# MCH_FPGA_Decoupling.net
KiCad netlist of a schematic drawn in Altium Designer
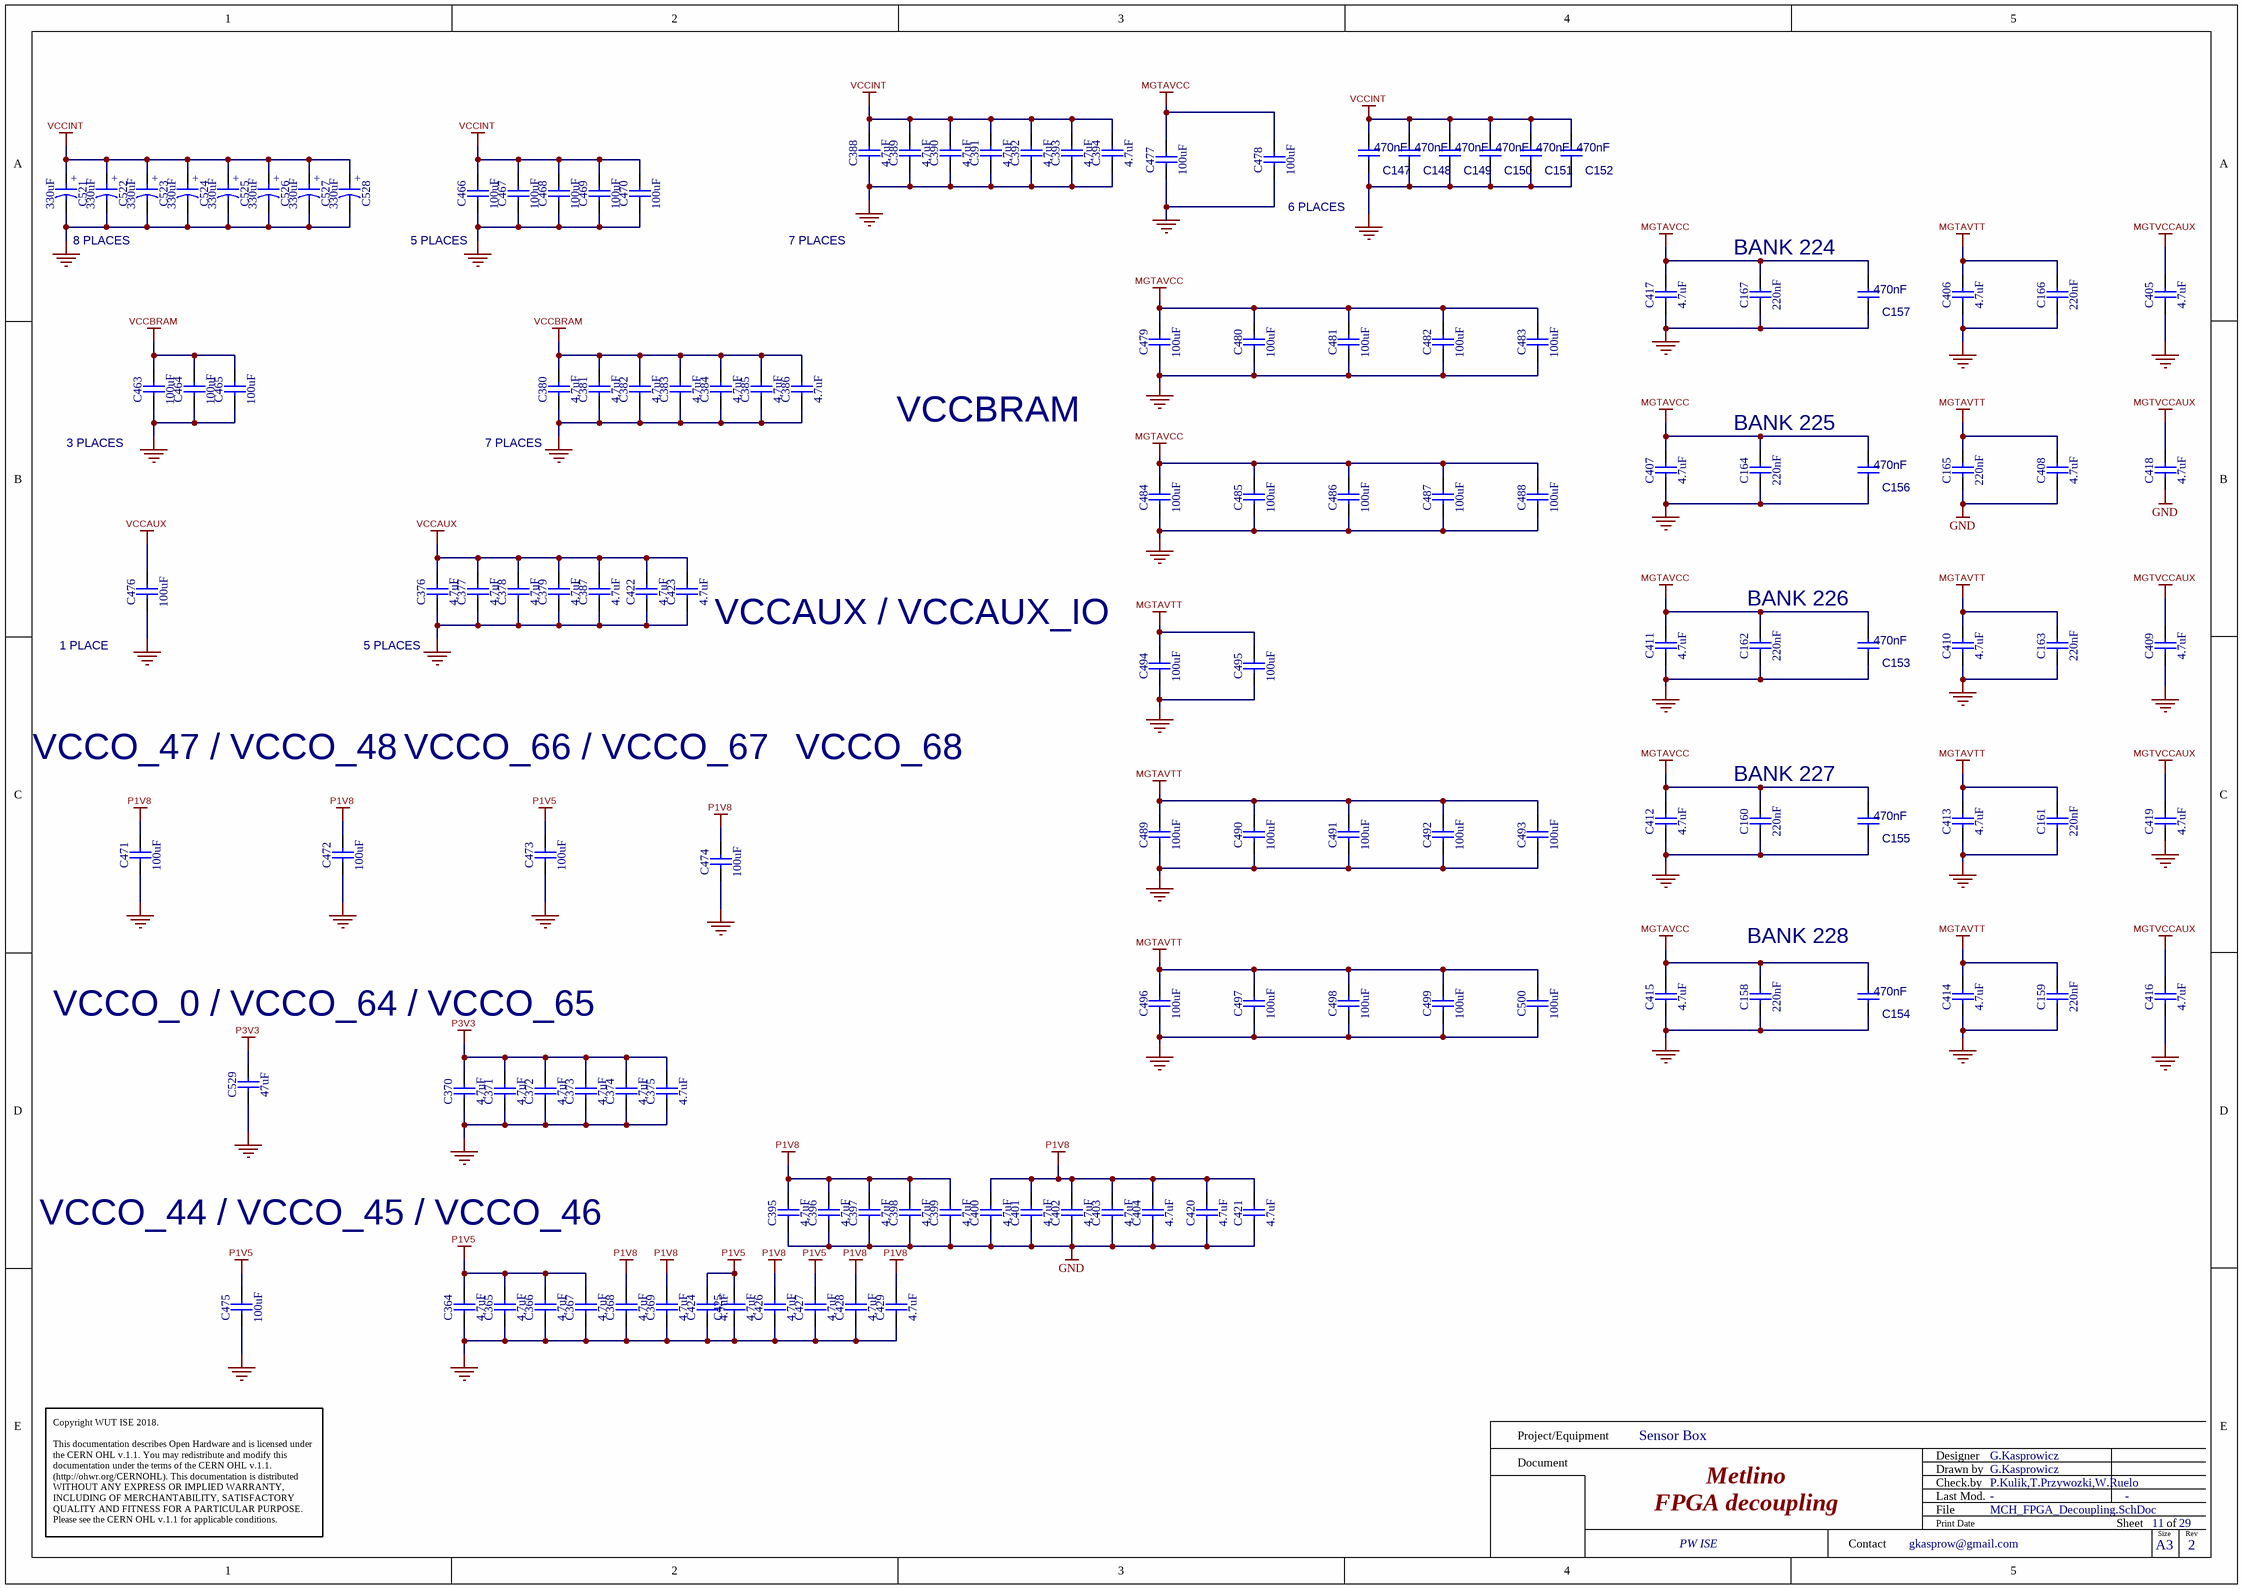
[diagram p0: MCH_FPGA_Decoupling.SchDoc]

(export (version "E")
  (design (tool "Eeschema 10.0.6"))
  (components
    (comp (ref "C147")
      (value "470nF")
      (footprint "CAPC0603X33N")
      (fields
        (field (name "$$NOTCOMMONPROPERTY_GENERAL PART NUMBER") "CC0201_470NF_4V_20%_X5R")
        (field (name "$$NOTCOMMONPROPERTY_MANUFACTURER1 PART NUMBER") "AMK063BJ474MP-F")
        (field (name "MANUFACTURER") "GENERIC")
      )
      (libsource (lib "altium-import") (part "root_1__*"))
    )
    (comp (ref "C148")
      (value "470nF")
      (footprint "CAPC0603X33N")
      (fields
        (field (name "$$NOTCOMMONPROPERTY_GENERAL PART NUMBER") "CC0201_470NF_4V_20%_X5R")
        (field (name "$$NOTCOMMONPROPERTY_MANUFACTURER1 PART NUMBER") "AMK063BJ474MP-F")
        (field (name "MANUFACTURER") "GENERIC")
      )
      (libsource (lib "altium-import") (part "root_1__*"))
    )
    (comp (ref "C149")
      (value "470nF")
      (footprint "CAPC0603X33N")
      (fields
        (field (name "$$NOTCOMMONPROPERTY_GENERAL PART NUMBER") "CC0201_470NF_4V_20%_X5R")
        (field (name "$$NOTCOMMONPROPERTY_MANUFACTURER1 PART NUMBER") "AMK063BJ474MP-F")
        (field (name "MANUFACTURER") "GENERIC")
      )
      (libsource (lib "altium-import") (part "root_1__*"))
    )
    (comp (ref "C150")
      (value "470nF")
      (footprint "CAPC0603X33N")
      (fields
        (field (name "$$NOTCOMMONPROPERTY_GENERAL PART NUMBER") "CC0201_470NF_4V_20%_X5R")
        (field (name "$$NOTCOMMONPROPERTY_MANUFACTURER1 PART NUMBER") "AMK063BJ474MP-F")
        (field (name "MANUFACTURER") "GENERIC")
      )
      (libsource (lib "altium-import") (part "root_1__*"))
    )
    (comp (ref "C151")
      (value "470nF")
      (footprint "CAPC0603X33N")
      (fields
        (field (name "$$NOTCOMMONPROPERTY_GENERAL PART NUMBER") "CC0201_470NF_4V_20%_X5R")
        (field (name "$$NOTCOMMONPROPERTY_MANUFACTURER1 PART NUMBER") "AMK063BJ474MP-F")
        (field (name "MANUFACTURER") "GENERIC")
      )
      (libsource (lib "altium-import") (part "root_1__*"))
    )
    (comp (ref "C152")
      (value "470nF")
      (footprint "CAPC0603X33N")
      (fields
        (field (name "$$NOTCOMMONPROPERTY_GENERAL PART NUMBER") "CC0201_470NF_4V_20%_X5R")
        (field (name "$$NOTCOMMONPROPERTY_MANUFACTURER1 PART NUMBER") "AMK063BJ474MP-F")
        (field (name "MANUFACTURER") "GENERIC")
      )
      (libsource (lib "altium-import") (part "root_1__*"))
    )
    (comp (ref "C153")
      (value "470nF")
      (footprint "CAPC0603X33N")
      (fields
        (field (name "$$NOTCOMMONPROPERTY_GENERAL PART NUMBER") "CC0201_470NF_4V_20%_X5R")
        (field (name "$$NOTCOMMONPROPERTY_MANUFACTURER1 PART NUMBER") "AMK063BJ474MP-F")
        (field (name "MANUFACTURER") "GENERIC")
      )
      (libsource (lib "altium-import") (part "root_1__*"))
    )
    (comp (ref "C154")
      (value "470nF")
      (footprint "CAPC0603X33N")
      (fields
        (field (name "$$NOTCOMMONPROPERTY_GENERAL PART NUMBER") "CC0201_470NF_4V_20%_X5R")
        (field (name "$$NOTCOMMONPROPERTY_MANUFACTURER1 PART NUMBER") "AMK063BJ474MP-F")
        (field (name "MANUFACTURER") "GENERIC")
      )
      (libsource (lib "altium-import") (part "root_1__*"))
    )
    (comp (ref "C155")
      (value "470nF")
      (footprint "CAPC0603X33N")
      (fields
        (field (name "$$NOTCOMMONPROPERTY_GENERAL PART NUMBER") "CC0201_470NF_4V_20%_X5R")
        (field (name "$$NOTCOMMONPROPERTY_MANUFACTURER1 PART NUMBER") "AMK063BJ474MP-F")
        (field (name "MANUFACTURER") "GENERIC")
      )
      (libsource (lib "altium-import") (part "root_1__*"))
    )
    (comp (ref "C156")
      (value "470nF")
      (footprint "CAPC0603X33N")
      (fields
        (field (name "$$NOTCOMMONPROPERTY_GENERAL PART NUMBER") "CC0201_470NF_4V_20%_X5R")
        (field (name "$$NOTCOMMONPROPERTY_MANUFACTURER1 PART NUMBER") "AMK063BJ474MP-F")
        (field (name "MANUFACTURER") "GENERIC")
      )
      (libsource (lib "altium-import") (part "root_1__*"))
    )
    (comp (ref "C157")
      (value "470nF")
      (footprint "CAPC0603X33N")
      (fields
        (field (name "$$NOTCOMMONPROPERTY_GENERAL PART NUMBER") "CC0201_470NF_4V_20%_X5R")
        (field (name "$$NOTCOMMONPROPERTY_MANUFACTURER1 PART NUMBER") "AMK063BJ474MP-F")
        (field (name "MANUFACTURER") "GENERIC")
      )
      (libsource (lib "altium-import") (part "root_1__*"))
    )
    (comp (ref "C158")
      (value "220nF")
      (footprint "CAPC0603X33N")
      (description "Non-polarised capacitor")
      (fields
        (field (name "MANUFACTURER PART NUMBER") "CC0201_220NF_6.3V_20%_X5R")
        (field (name "MANUFACTURER") "GENERIC")
        (field (name "AUTHOR") "CERN DEM JLC")
      )
      (libsource (lib "Capacitors") (part "Capacitor - non polarized"))
    )
    (comp (ref "C159")
      (value "220nF")
      (footprint "CAPC0603X33N")
      (description "Non-polarised capacitor")
      (fields
        (field (name "MANUFACTURER PART NUMBER") "CC0201_220NF_6.3V_20%_X5R")
        (field (name "MANUFACTURER") "GENERIC")
        (field (name "AUTHOR") "CERN DEM JLC")
      )
      (libsource (lib "Capacitors") (part "Capacitor - non polarized"))
    )
    (comp (ref "C160")
      (value "220nF")
      (footprint "CAPC0603X33N")
      (description "Non-polarised capacitor")
      (fields
        (field (name "MANUFACTURER PART NUMBER") "CC0201_220NF_6.3V_20%_X5R")
        (field (name "MANUFACTURER") "GENERIC")
        (field (name "AUTHOR") "CERN DEM JLC")
      )
      (libsource (lib "Capacitors") (part "Capacitor - non polarized"))
    )
    (comp (ref "C161")
      (value "220nF")
      (footprint "CAPC0603X33N")
      (description "Non-polarised capacitor")
      (fields
        (field (name "MANUFACTURER PART NUMBER") "CC0201_220NF_6.3V_20%_X5R")
        (field (name "MANUFACTURER") "GENERIC")
        (field (name "AUTHOR") "CERN DEM JLC")
      )
      (libsource (lib "Capacitors") (part "Capacitor - non polarized"))
    )
    (comp (ref "C162")
      (value "220nF")
      (footprint "CAPC0603X33N")
      (description "Non-polarised capacitor")
      (fields
        (field (name "MANUFACTURER PART NUMBER") "CC0201_220NF_6.3V_20%_X5R")
        (field (name "MANUFACTURER") "GENERIC")
        (field (name "AUTHOR") "CERN DEM JLC")
      )
      (libsource (lib "Capacitors") (part "Capacitor - non polarized"))
    )
    (comp (ref "C163")
      (value "220nF")
      (footprint "CAPC0603X33N")
      (description "Non-polarised capacitor")
      (fields
        (field (name "MANUFACTURER PART NUMBER") "CC0201_220NF_6.3V_20%_X5R")
        (field (name "MANUFACTURER") "GENERIC")
        (field (name "AUTHOR") "CERN DEM JLC")
      )
      (libsource (lib "Capacitors") (part "Capacitor - non polarized"))
    )
    (comp (ref "C164")
      (value "220nF")
      (footprint "CAPC0603X33N")
      (description "Non-polarised capacitor")
      (fields
        (field (name "MANUFACTURER PART NUMBER") "CC0201_220NF_6.3V_20%_X5R")
        (field (name "MANUFACTURER") "GENERIC")
        (field (name "AUTHOR") "CERN DEM JLC")
      )
      (libsource (lib "Capacitors") (part "Capacitor - non polarized"))
    )
    (comp (ref "C165")
      (value "220nF")
      (footprint "CAPC0603X33N")
      (description "Non-polarised capacitor")
      (fields
        (field (name "MANUFACTURER PART NUMBER") "CC0201_220NF_6.3V_20%_X5R")
        (field (name "MANUFACTURER") "GENERIC")
        (field (name "AUTHOR") "CERN DEM JLC")
      )
      (libsource (lib "Capacitors") (part "Capacitor - non polarized"))
    )
    (comp (ref "C166")
      (value "220nF")
      (footprint "CAPC0603X33N")
      (description "Non-polarised capacitor")
      (fields
        (field (name "MANUFACTURER PART NUMBER") "CC0201_220NF_6.3V_20%_X5R")
        (field (name "MANUFACTURER") "GENERIC")
        (field (name "AUTHOR") "CERN DEM JLC")
      )
      (libsource (lib "Capacitors") (part "Capacitor - non polarized"))
    )
    (comp (ref "C167")
      (value "220nF")
      (footprint "CAPC0603X33N")
      (description "Non-polarised capacitor")
      (fields
        (field (name "MANUFACTURER PART NUMBER") "CC0201_220NF_6.3V_20%_X5R")
        (field (name "MANUFACTURER") "GENERIC")
        (field (name "AUTHOR") "CERN DEM JLC")
      )
      (libsource (lib "Capacitors") (part "Capacitor - non polarized"))
    )
    (comp (ref "C364")
      (value "4.7uF")
      (footprint "CAPC1005X55N")
      (description "Non-polarised capacitor")
      (fields
        (field (name "MANUFACTURER PART NUMBER") "CC0402_4.7UF_6.3V_20%_X5R")
        (field (name "MANUFACTURER") "GENERIC")
        (field (name "AUTHOR") "CERN DEM JLC")
      )
      (libsource (lib "Capacitors") (part "Capacitor - non polarized"))
    )
    (comp (ref "C365")
      (value "4.7uF")
      (footprint "CAPC1005X55N")
      (description "Non-polarised capacitor")
      (fields
        (field (name "MANUFACTURER PART NUMBER") "CC0402_4.7UF_6.3V_20%_X5R")
        (field (name "MANUFACTURER") "GENERIC")
        (field (name "AUTHOR") "CERN DEM JLC")
      )
      (libsource (lib "Capacitors") (part "Capacitor - non polarized"))
    )
    (comp (ref "C366")
      (value "4.7uF")
      (footprint "CAPC1005X55N")
      (description "Non-polarised capacitor")
      (fields
        (field (name "MANUFACTURER PART NUMBER") "CC0402_4.7UF_6.3V_20%_X5R")
        (field (name "MANUFACTURER") "GENERIC")
        (field (name "AUTHOR") "CERN DEM JLC")
      )
      (libsource (lib "Capacitors") (part "Capacitor - non polarized"))
    )
    (comp (ref "C367")
      (value "4.7uF")
      (footprint "CAPC1005X55N")
      (description "Non-polarised capacitor")
      (fields
        (field (name "MANUFACTURER PART NUMBER") "CC0402_4.7UF_6.3V_20%_X5R")
        (field (name "MANUFACTURER") "GENERIC")
        (field (name "AUTHOR") "CERN DEM JLC")
      )
      (libsource (lib "Capacitors") (part "Capacitor - non polarized"))
    )
    (comp (ref "C368")
      (value "4.7uF")
      (footprint "CAPC1005X55N")
      (description "Non-polarised capacitor")
      (fields
        (field (name "MANUFACTURER PART NUMBER") "CC0402_4.7UF_6.3V_20%_X5R")
        (field (name "MANUFACTURER") "GENERIC")
        (field (name "AUTHOR") "CERN DEM JLC")
      )
      (libsource (lib "Capacitors") (part "Capacitor - non polarized"))
    )
    (comp (ref "C369")
      (value "4.7uF")
      (footprint "CAPC1005X55N")
      (description "Non-polarised capacitor")
      (fields
        (field (name "MANUFACTURER PART NUMBER") "CC0402_4.7UF_6.3V_20%_X5R")
        (field (name "MANUFACTURER") "GENERIC")
        (field (name "AUTHOR") "CERN DEM JLC")
      )
      (libsource (lib "Capacitors") (part "Capacitor - non polarized"))
    )
    (comp (ref "C370")
      (value "4.7uF")
      (footprint "CAPC1005X55N")
      (description "Non-polarised capacitor")
      (fields
        (field (name "MANUFACTURER PART NUMBER") "CC0402_4.7UF_6.3V_20%_X5R")
        (field (name "MANUFACTURER") "GENERIC")
        (field (name "AUTHOR") "CERN DEM JLC")
      )
      (libsource (lib "Capacitors") (part "Capacitor - non polarized"))
    )
    (comp (ref "C371")
      (value "4.7uF")
      (footprint "CAPC1005X55N")
      (description "Non-polarised capacitor")
      (fields
        (field (name "MANUFACTURER PART NUMBER") "CC0402_4.7UF_6.3V_20%_X5R")
        (field (name "MANUFACTURER") "GENERIC")
        (field (name "AUTHOR") "CERN DEM JLC")
      )
      (libsource (lib "Capacitors") (part "Capacitor - non polarized"))
    )
    (comp (ref "C372")
      (value "4.7uF")
      (footprint "CAPC1005X55N")
      (description "Non-polarised capacitor")
      (fields
        (field (name "MANUFACTURER PART NUMBER") "CC0402_4.7UF_6.3V_20%_X5R")
        (field (name "MANUFACTURER") "GENERIC")
        (field (name "AUTHOR") "CERN DEM JLC")
      )
      (libsource (lib "Capacitors") (part "Capacitor - non polarized"))
    )
    (comp (ref "C373")
      (value "4.7uF")
      (footprint "CAPC1005X55N")
      (description "Non-polarised capacitor")
      (fields
        (field (name "MANUFACTURER PART NUMBER") "CC0402_4.7UF_6.3V_20%_X5R")
        (field (name "MANUFACTURER") "GENERIC")
        (field (name "AUTHOR") "CERN DEM JLC")
      )
      (libsource (lib "Capacitors") (part "Capacitor - non polarized"))
    )
    (comp (ref "C374")
      (value "4.7uF")
      (footprint "CAPC1005X55N")
      (description "Non-polarised capacitor")
      (fields
        (field (name "MANUFACTURER PART NUMBER") "CC0402_4.7UF_6.3V_20%_X5R")
        (field (name "MANUFACTURER") "GENERIC")
        (field (name "AUTHOR") "CERN DEM JLC")
      )
      (libsource (lib "Capacitors") (part "Capacitor - non polarized"))
    )
    (comp (ref "C375")
      (value "4.7uF")
      (footprint "CAPC1005X55N")
      (description "Non-polarised capacitor")
      (fields
        (field (name "MANUFACTURER PART NUMBER") "CC0402_4.7UF_6.3V_20%_X5R")
        (field (name "MANUFACTURER") "GENERIC")
        (field (name "AUTHOR") "CERN DEM JLC")
      )
      (libsource (lib "Capacitors") (part "Capacitor - non polarized"))
    )
    (comp (ref "C376")
      (value "4.7uF")
      (footprint "CAPC1005X55N")
      (description "Non-polarised capacitor")
      (fields
        (field (name "MANUFACTURER PART NUMBER") "CC0402_4.7UF_6.3V_20%_X5R")
        (field (name "MANUFACTURER") "GENERIC")
        (field (name "AUTHOR") "CERN DEM JLC")
      )
      (libsource (lib "Capacitors") (part "Capacitor - non polarized"))
    )
    (comp (ref "C377")
      (value "4.7uF")
      (footprint "CAPC1005X55N")
      (description "Non-polarised capacitor")
      (fields
        (field (name "MANUFACTURER PART NUMBER") "CC0402_4.7UF_6.3V_20%_X5R")
        (field (name "MANUFACTURER") "GENERIC")
        (field (name "AUTHOR") "CERN DEM JLC")
      )
      (libsource (lib "Capacitors") (part "Capacitor - non polarized"))
    )
    (comp (ref "C378")
      (value "4.7uF")
      (footprint "CAPC1005X55N")
      (description "Non-polarised capacitor")
      (fields
        (field (name "MANUFACTURER PART NUMBER") "CC0402_4.7UF_6.3V_20%_X5R")
        (field (name "MANUFACTURER") "GENERIC")
        (field (name "AUTHOR") "CERN DEM JLC")
      )
      (libsource (lib "Capacitors") (part "Capacitor - non polarized"))
    )
    (comp (ref "C379")
      (value "4.7uF")
      (footprint "CAPC1005X55N")
      (description "Non-polarised capacitor")
      (fields
        (field (name "MANUFACTURER PART NUMBER") "CC0402_4.7UF_6.3V_20%_X5R")
        (field (name "MANUFACTURER") "GENERIC")
        (field (name "AUTHOR") "CERN DEM JLC")
      )
      (libsource (lib "Capacitors") (part "Capacitor - non polarized"))
    )
    (comp (ref "C380")
      (value "4.7uF")
      (footprint "CAPC1005X55N")
      (description "Non-polarised capacitor")
      (fields
        (field (name "MANUFACTURER PART NUMBER") "CC0402_4.7UF_6.3V_20%_X5R")
        (field (name "MANUFACTURER") "GENERIC")
        (field (name "AUTHOR") "CERN DEM JLC")
      )
      (libsource (lib "Capacitors") (part "Capacitor - non polarized"))
    )
    (comp (ref "C381")
      (value "4.7uF")
      (footprint "CAPC1005X55N")
      (description "Non-polarised capacitor")
      (fields
        (field (name "MANUFACTURER PART NUMBER") "CC0402_4.7UF_6.3V_20%_X5R")
        (field (name "MANUFACTURER") "GENERIC")
        (field (name "AUTHOR") "CERN DEM JLC")
      )
      (libsource (lib "Capacitors") (part "Capacitor - non polarized"))
    )
    (comp (ref "C382")
      (value "4.7uF")
      (footprint "CAPC1005X55N")
      (description "Non-polarised capacitor")
      (fields
        (field (name "MANUFACTURER PART NUMBER") "CC0402_4.7UF_6.3V_20%_X5R")
        (field (name "MANUFACTURER") "GENERIC")
        (field (name "AUTHOR") "CERN DEM JLC")
      )
      (libsource (lib "Capacitors") (part "Capacitor - non polarized"))
    )
    (comp (ref "C383")
      (value "4.7uF")
      (footprint "CAPC1005X55N")
      (description "Non-polarised capacitor")
      (fields
        (field (name "MANUFACTURER PART NUMBER") "CC0402_4.7UF_6.3V_20%_X5R")
        (field (name "MANUFACTURER") "GENERIC")
        (field (name "AUTHOR") "CERN DEM JLC")
      )
      (libsource (lib "Capacitors") (part "Capacitor - non polarized"))
    )
    (comp (ref "C384")
      (value "4.7uF")
      (footprint "CAPC1005X55N")
      (description "Non-polarised capacitor")
      (fields
        (field (name "MANUFACTURER PART NUMBER") "CC0402_4.7UF_6.3V_20%_X5R")
        (field (name "MANUFACTURER") "GENERIC")
        (field (name "AUTHOR") "CERN DEM JLC")
      )
      (libsource (lib "Capacitors") (part "Capacitor - non polarized"))
    )
    (comp (ref "C385")
      (value "4.7uF")
      (footprint "CAPC1005X55N")
      (description "Non-polarised capacitor")
      (fields
        (field (name "MANUFACTURER PART NUMBER") "CC0402_4.7UF_6.3V_20%_X5R")
        (field (name "MANUFACTURER") "GENERIC")
        (field (name "AUTHOR") "CERN DEM JLC")
      )
      (libsource (lib "Capacitors") (part "Capacitor - non polarized"))
    )
    (comp (ref "C386")
      (value "4.7uF")
      (footprint "CAPC1005X55N")
      (description "Non-polarised capacitor")
      (fields
        (field (name "MANUFACTURER PART NUMBER") "CC0402_4.7UF_6.3V_20%_X5R")
        (field (name "MANUFACTURER") "GENERIC")
        (field (name "AUTHOR") "CERN DEM JLC")
      )
      (libsource (lib "Capacitors") (part "Capacitor - non polarized"))
    )
    (comp (ref "C387")
      (value "4.7uF")
      (footprint "CAPC1005X55N")
      (description "Non-polarised capacitor")
      (fields
        (field (name "MANUFACTURER PART NUMBER") "CC0402_4.7UF_6.3V_20%_X5R")
        (field (name "MANUFACTURER") "GENERIC")
        (field (name "AUTHOR") "CERN DEM JLC")
      )
      (libsource (lib "Capacitors") (part "Capacitor - non polarized"))
    )
    (comp (ref "C388")
      (value "4.7uF")
      (footprint "CAPC1005X55N")
      (description "Non-polarised capacitor")
      (fields
        (field (name "MANUFACTURER PART NUMBER") "CC0402_4.7UF_6.3V_20%_X5R")
        (field (name "MANUFACTURER") "GENERIC")
        (field (name "AUTHOR") "CERN DEM JLC")
      )
      (libsource (lib "Capacitors") (part "Capacitor - non polarized"))
    )
    (comp (ref "C389")
      (value "4.7uF")
      (footprint "CAPC1005X55N")
      (description "Non-polarised capacitor")
      (fields
        (field (name "MANUFACTURER PART NUMBER") "CC0402_4.7UF_6.3V_20%_X5R")
        (field (name "MANUFACTURER") "GENERIC")
        (field (name "AUTHOR") "CERN DEM JLC")
      )
      (libsource (lib "Capacitors") (part "Capacitor - non polarized"))
    )
    (comp (ref "C390")
      (value "4.7uF")
      (footprint "CAPC1005X55N")
      (description "Non-polarised capacitor")
      (fields
        (field (name "MANUFACTURER PART NUMBER") "CC0402_4.7UF_6.3V_20%_X5R")
        (field (name "MANUFACTURER") "GENERIC")
        (field (name "AUTHOR") "CERN DEM JLC")
      )
      (libsource (lib "Capacitors") (part "Capacitor - non polarized"))
    )
    (comp (ref "C391")
      (value "4.7uF")
      (footprint "CAPC1005X55N")
      (description "Non-polarised capacitor")
      (fields
        (field (name "MANUFACTURER PART NUMBER") "CC0402_4.7UF_6.3V_20%_X5R")
        (field (name "MANUFACTURER") "GENERIC")
        (field (name "AUTHOR") "CERN DEM JLC")
      )
      (libsource (lib "Capacitors") (part "Capacitor - non polarized"))
    )
    (comp (ref "C392")
      (value "4.7uF")
      (footprint "CAPC1005X55N")
      (description "Non-polarised capacitor")
      (fields
        (field (name "MANUFACTURER PART NUMBER") "CC0402_4.7UF_6.3V_20%_X5R")
        (field (name "MANUFACTURER") "GENERIC")
        (field (name "AUTHOR") "CERN DEM JLC")
      )
      (libsource (lib "Capacitors") (part "Capacitor - non polarized"))
    )
    (comp (ref "C393")
      (value "4.7uF")
      (footprint "CAPC1005X55N")
      (description "Non-polarised capacitor")
      (fields
        (field (name "MANUFACTURER PART NUMBER") "CC0402_4.7UF_6.3V_20%_X5R")
        (field (name "MANUFACTURER") "GENERIC")
        (field (name "AUTHOR") "CERN DEM JLC")
      )
      (libsource (lib "Capacitors") (part "Capacitor - non polarized"))
    )
    (comp (ref "C394")
      (value "4.7uF")
      (footprint "CAPC1005X55N")
      (description "Non-polarised capacitor")
      (fields
        (field (name "MANUFACTURER PART NUMBER") "CC0402_4.7UF_6.3V_20%_X5R")
        (field (name "MANUFACTURER") "GENERIC")
        (field (name "AUTHOR") "CERN DEM JLC")
      )
      (libsource (lib "Capacitors") (part "Capacitor - non polarized"))
    )
    (comp (ref "C395")
      (value "4.7uF")
      (footprint "CAPC1005X55N")
      (description "Non-polarised capacitor")
      (fields
        (field (name "MANUFACTURER PART NUMBER") "CC0402_4.7UF_6.3V_20%_X5R")
        (field (name "MANUFACTURER") "GENERIC")
        (field (name "AUTHOR") "CERN DEM JLC")
      )
      (libsource (lib "Capacitors") (part "Capacitor - non polarized"))
    )
    (comp (ref "C396")
      (value "4.7uF")
      (footprint "CAPC1005X55N")
      (description "Non-polarised capacitor")
      (fields
        (field (name "MANUFACTURER PART NUMBER") "CC0402_4.7UF_6.3V_20%_X5R")
        (field (name "MANUFACTURER") "GENERIC")
        (field (name "AUTHOR") "CERN DEM JLC")
      )
      (libsource (lib "Capacitors") (part "Capacitor - non polarized"))
    )
    (comp (ref "C397")
      (value "4.7uF")
      (footprint "CAPC1005X55N")
      (description "Non-polarised capacitor")
      (fields
        (field (name "MANUFACTURER PART NUMBER") "CC0402_4.7UF_6.3V_20%_X5R")
        (field (name "MANUFACTURER") "GENERIC")
        (field (name "AUTHOR") "CERN DEM JLC")
      )
      (libsource (lib "Capacitors") (part "Capacitor - non polarized"))
    )
    (comp (ref "C398")
      (value "4.7uF")
      (footprint "CAPC1005X55N")
      (description "Non-polarised capacitor")
      (fields
        (field (name "MANUFACTURER PART NUMBER") "CC0402_4.7UF_6.3V_20%_X5R")
        (field (name "MANUFACTURER") "GENERIC")
        (field (name "AUTHOR") "CERN DEM JLC")
      )
      (libsource (lib "Capacitors") (part "Capacitor - non polarized"))
    )
    (comp (ref "C399")
      (value "4.7uF")
      (footprint "CAPC1005X55N")
      (description "Non-polarised capacitor")
      (fields
        (field (name "MANUFACTURER PART NUMBER") "CC0402_4.7UF_6.3V_20%_X5R")
        (field (name "MANUFACTURER") "GENERIC")
        (field (name "AUTHOR") "CERN DEM JLC")
      )
      (libsource (lib "Capacitors") (part "Capacitor - non polarized"))
    )
    (comp (ref "C400")
      (value "4.7uF")
      (footprint "CAPC1005X55N")
      (description "Non-polarised capacitor")
      (fields
        (field (name "MANUFACTURER PART NUMBER") "CC0402_4.7UF_6.3V_20%_X5R")
        (field (name "MANUFACTURER") "GENERIC")
        (field (name "AUTHOR") "CERN DEM JLC")
      )
      (libsource (lib "Capacitors") (part "Capacitor - non polarized"))
    )
    (comp (ref "C401")
      (value "4.7uF")
      (footprint "CAPC1005X55N")
      (description "Non-polarised capacitor")
      (fields
        (field (name "MANUFACTURER PART NUMBER") "CC0402_4.7UF_6.3V_20%_X5R")
        (field (name "MANUFACTURER") "GENERIC")
        (field (name "AUTHOR") "CERN DEM JLC")
      )
      (libsource (lib "Capacitors") (part "Capacitor - non polarized"))
    )
    (comp (ref "C402")
      (value "4.7uF")
      (footprint "CAPC1005X55N")
      (description "Non-polarised capacitor")
      (fields
        (field (name "MANUFACTURER PART NUMBER") "CC0402_4.7UF_6.3V_20%_X5R")
        (field (name "MANUFACTURER") "GENERIC")
        (field (name "AUTHOR") "CERN DEM JLC")
      )
      (libsource (lib "Capacitors") (part "Capacitor - non polarized"))
    )
    (comp (ref "C403")
      (value "4.7uF")
      (footprint "CAPC1005X55N")
      (description "Non-polarised capacitor")
      (fields
        (field (name "MANUFACTURER PART NUMBER") "CC0402_4.7UF_6.3V_20%_X5R")
        (field (name "MANUFACTURER") "GENERIC")
        (field (name "AUTHOR") "CERN DEM JLC")
      )
      (libsource (lib "Capacitors") (part "Capacitor - non polarized"))
    )
    (comp (ref "C404")
      (value "4.7uF")
      (footprint "CAPC1005X55N")
      (description "Non-polarised capacitor")
      (fields
        (field (name "MANUFACTURER PART NUMBER") "CC0402_4.7UF_6.3V_20%_X5R")
        (field (name "MANUFACTURER") "GENERIC")
        (field (name "AUTHOR") "CERN DEM JLC")
      )
      (libsource (lib "Capacitors") (part "Capacitor - non polarized"))
    )
    (comp (ref "C405")
      (value "4.7uF")
      (footprint "CAPC1005X55N")
      (description "Non-polarised capacitor")
      (fields
        (field (name "MANUFACTURER PART NUMBER") "CC0402_4.7UF_6.3V_20%_X5R")
        (field (name "MANUFACTURER") "GENERIC")
        (field (name "AUTHOR") "CERN DEM JLC")
      )
      (libsource (lib "Capacitors") (part "Capacitor - non polarized"))
    )
    (comp (ref "C406")
      (value "4.7uF")
      (footprint "CAPC1005X55N")
      (description "Non-polarised capacitor")
      (fields
        (field (name "MANUFACTURER PART NUMBER") "CC0402_4.7UF_6.3V_20%_X5R")
        (field (name "MANUFACTURER") "GENERIC")
        (field (name "AUTHOR") "CERN DEM JLC")
      )
      (libsource (lib "Capacitors") (part "Capacitor - non polarized"))
    )
    (comp (ref "C407")
      (value "4.7uF")
      (footprint "CAPC1005X55N")
      (description "Non-polarised capacitor")
      (fields
        (field (name "MANUFACTURER PART NUMBER") "CC0402_4.7UF_6.3V_20%_X5R")
        (field (name "MANUFACTURER") "GENERIC")
        (field (name "AUTHOR") "CERN DEM JLC")
      )
      (libsource (lib "Capacitors") (part "Capacitor - non polarized"))
    )
    (comp (ref "C408")
      (value "4.7uF")
      (footprint "CAPC1005X55N")
      (description "Non-polarised capacitor")
      (fields
        (field (name "MANUFACTURER PART NUMBER") "CC0402_4.7UF_6.3V_20%_X5R")
        (field (name "MANUFACTURER") "GENERIC")
        (field (name "AUTHOR") "CERN DEM JLC")
      )
      (libsource (lib "Capacitors") (part "Capacitor - non polarized"))
    )
    (comp (ref "C409")
      (value "4.7uF")
      (footprint "CAPC1005X55N")
      (description "Non-polarised capacitor")
      (fields
        (field (name "MANUFACTURER PART NUMBER") "CC0402_4.7UF_6.3V_20%_X5R")
        (field (name "MANUFACTURER") "GENERIC")
        (field (name "AUTHOR") "CERN DEM JLC")
      )
      (libsource (lib "Capacitors") (part "Capacitor - non polarized"))
    )
    (comp (ref "C410")
      (value "4.7uF")
      (footprint "CAPC1005X55N")
      (description "Non-polarised capacitor")
      (fields
        (field (name "MANUFACTURER PART NUMBER") "CC0402_4.7UF_6.3V_20%_X5R")
        (field (name "MANUFACTURER") "GENERIC")
        (field (name "AUTHOR") "CERN DEM JLC")
      )
      (libsource (lib "Capacitors") (part "Capacitor - non polarized"))
    )
    (comp (ref "C411")
      (value "4.7uF")
      (footprint "CAPC1005X55N")
      (description "Non-polarised capacitor")
      (fields
        (field (name "MANUFACTURER PART NUMBER") "CC0402_4.7UF_6.3V_20%_X5R")
        (field (name "MANUFACTURER") "GENERIC")
        (field (name "AUTHOR") "CERN DEM JLC")
      )
      (libsource (lib "Capacitors") (part "Capacitor - non polarized"))
    )
    (comp (ref "C412")
      (value "4.7uF")
      (footprint "CAPC1005X55N")
      (description "Non-polarised capacitor")
      (fields
        (field (name "MANUFACTURER PART NUMBER") "CC0402_4.7UF_6.3V_20%_X5R")
        (field (name "MANUFACTURER") "GENERIC")
        (field (name "AUTHOR") "CERN DEM JLC")
      )
      (libsource (lib "Capacitors") (part "Capacitor - non polarized"))
    )
    (comp (ref "C413")
      (value "4.7uF")
      (footprint "CAPC1005X55N")
      (description "Non-polarised capacitor")
      (fields
        (field (name "MANUFACTURER PART NUMBER") "CC0402_4.7UF_6.3V_20%_X5R")
        (field (name "MANUFACTURER") "GENERIC")
        (field (name "AUTHOR") "CERN DEM JLC")
      )
      (libsource (lib "Capacitors") (part "Capacitor - non polarized"))
    )
    (comp (ref "C414")
      (value "4.7uF")
      (footprint "CAPC1005X55N")
      (description "Non-polarised capacitor")
      (fields
        (field (name "MANUFACTURER PART NUMBER") "CC0402_4.7UF_6.3V_20%_X5R")
        (field (name "MANUFACTURER") "GENERIC")
        (field (name "AUTHOR") "CERN DEM JLC")
      )
      (libsource (lib "Capacitors") (part "Capacitor - non polarized"))
    )
    (comp (ref "C415")
      (value "4.7uF")
      (footprint "CAPC1005X55N")
      (description "Non-polarised capacitor")
      (fields
        (field (name "MANUFACTURER PART NUMBER") "CC0402_4.7UF_6.3V_20%_X5R")
        (field (name "MANUFACTURER") "GENERIC")
        (field (name "AUTHOR") "CERN DEM JLC")
      )
      (libsource (lib "Capacitors") (part "Capacitor - non polarized"))
    )
    (comp (ref "C416")
      (value "4.7uF")
      (footprint "CAPC1005X55N")
      (description "Non-polarised capacitor")
      (fields
        (field (name "MANUFACTURER PART NUMBER") "CC0402_4.7UF_6.3V_20%_X5R")
        (field (name "MANUFACTURER") "GENERIC")
        (field (name "AUTHOR") "CERN DEM JLC")
      )
      (libsource (lib "Capacitors") (part "Capacitor - non polarized"))
    )
    (comp (ref "C417")
      (value "4.7uF")
      (footprint "CAPC1005X55N")
      (description "Non-polarised capacitor")
      (fields
        (field (name "MANUFACTURER PART NUMBER") "CC0402_4.7UF_6.3V_20%_X5R")
        (field (name "MANUFACTURER") "GENERIC")
        (field (name "AUTHOR") "CERN DEM JLC")
      )
      (libsource (lib "Capacitors") (part "Capacitor - non polarized"))
    )
    (comp (ref "C418")
      (value "4.7uF")
      (footprint "CAPC1005X55N")
      (description "Non-polarised capacitor")
      (fields
        (field (name "MANUFACTURER PART NUMBER") "CC0402_4.7UF_6.3V_20%_X5R")
        (field (name "MANUFACTURER") "GENERIC")
        (field (name "AUTHOR") "CERN DEM JLC")
      )
      (libsource (lib "Capacitors") (part "Capacitor - non polarized"))
    )
    (comp (ref "C419")
      (value "4.7uF")
      (footprint "CAPC1005X55N")
      (description "Non-polarised capacitor")
      (fields
        (field (name "MANUFACTURER PART NUMBER") "CC0402_4.7UF_6.3V_20%_X5R")
        (field (name "MANUFACTURER") "GENERIC")
        (field (name "AUTHOR") "CERN DEM JLC")
      )
      (libsource (lib "Capacitors") (part "Capacitor - non polarized"))
    )
    (comp (ref "C420")
      (value "4.7uF")
      (footprint "CAPC1005X55N")
      (description "Non-polarised capacitor")
      (fields
        (field (name "MANUFACTURER PART NUMBER") "CC0402_4.7UF_6.3V_20%_X5R")
        (field (name "MANUFACTURER") "GENERIC")
        (field (name "AUTHOR") "CERN DEM JLC")
      )
      (libsource (lib "Capacitors") (part "Capacitor - non polarized"))
    )
    (comp (ref "C421")
      (value "4.7uF")
      (footprint "CAPC1005X55N")
      (description "Non-polarised capacitor")
      (fields
        (field (name "MANUFACTURER PART NUMBER") "CC0402_4.7UF_6.3V_20%_X5R")
        (field (name "MANUFACTURER") "GENERIC")
        (field (name "AUTHOR") "CERN DEM JLC")
      )
      (libsource (lib "Capacitors") (part "Capacitor - non polarized"))
    )
    (comp (ref "C422")
      (value "4.7uF")
      (footprint "CAPC1005X55N")
      (description "Non-polarised capacitor")
      (fields
        (field (name "MANUFACTURER PART NUMBER") "CC0402_4.7UF_6.3V_20%_X5R")
        (field (name "MANUFACTURER") "GENERIC")
        (field (name "AUTHOR") "CERN DEM JLC")
      )
      (libsource (lib "Capacitors") (part "Capacitor - non polarized"))
    )
    (comp (ref "C423")
      (value "4.7uF")
      (footprint "CAPC1005X55N")
      (description "Non-polarised capacitor")
      (fields
        (field (name "MANUFACTURER PART NUMBER") "CC0402_4.7UF_6.3V_20%_X5R")
        (field (name "MANUFACTURER") "GENERIC")
        (field (name "AUTHOR") "CERN DEM JLC")
      )
      (libsource (lib "Capacitors") (part "Capacitor - non polarized"))
    )
    (comp (ref "C424")
      (value "4.7uF")
      (footprint "CAPC1005X55N")
      (description "Non-polarised capacitor")
      (fields
        (field (name "MANUFACTURER PART NUMBER") "CC0402_4.7UF_6.3V_20%_X5R")
        (field (name "MANUFACTURER") "GENERIC")
        (field (name "AUTHOR") "CERN DEM JLC")
      )
      (libsource (lib "Capacitors") (part "Capacitor - non polarized"))
    )
    (comp (ref "C425")
      (value "4.7uF")
      (footprint "CAPC1005X55N")
      (description "Non-polarised capacitor")
      (fields
        (field (name "MANUFACTURER PART NUMBER") "CC0402_4.7UF_6.3V_20%_X5R")
        (field (name "MANUFACTURER") "GENERIC")
        (field (name "AUTHOR") "CERN DEM JLC")
      )
      (libsource (lib "Capacitors") (part "Capacitor - non polarized"))
    )
    (comp (ref "C426")
      (value "4.7uF")
      (footprint "CAPC1005X55N")
      (description "Non-polarised capacitor")
      (fields
        (field (name "MANUFACTURER PART NUMBER") "CC0402_4.7UF_6.3V_20%_X5R")
        (field (name "MANUFACTURER") "GENERIC")
        (field (name "AUTHOR") "CERN DEM JLC")
      )
      (libsource (lib "Capacitors") (part "Capacitor - non polarized"))
    )
    (comp (ref "C427")
      (value "4.7uF")
      (footprint "CAPC1005X55N")
      (description "Non-polarised capacitor")
      (fields
        (field (name "MANUFACTURER PART NUMBER") "CC0402_4.7UF_6.3V_20%_X5R")
        (field (name "MANUFACTURER") "GENERIC")
        (field (name "AUTHOR") "CERN DEM JLC")
      )
      (libsource (lib "Capacitors") (part "Capacitor - non polarized"))
    )
    (comp (ref "C428")
      (value "4.7uF")
      (footprint "CAPC1005X55N")
      (description "Non-polarised capacitor")
      (fields
        (field (name "MANUFACTURER PART NUMBER") "CC0402_4.7UF_6.3V_20%_X5R")
        (field (name "MANUFACTURER") "GENERIC")
        (field (name "AUTHOR") "CERN DEM JLC")
      )
      (libsource (lib "Capacitors") (part "Capacitor - non polarized"))
    )
    (comp (ref "C429")
      (value "4.7uF")
      (footprint "CAPC1005X55N")
      (description "Non-polarised capacitor")
      (fields
        (field (name "MANUFACTURER PART NUMBER") "CC0402_4.7UF_6.3V_20%_X5R")
        (field (name "MANUFACTURER") "GENERIC")
        (field (name "AUTHOR") "CERN DEM JLC")
      )
      (libsource (lib "Capacitors") (part "Capacitor - non polarized"))
    )
    (comp (ref "C463")
      (value "100uF")
      (footprint "CAPC3216X180N")
      (description "Non-polarised capacitor")
      (fields
        (field (name "MANUFACTURER PART NUMBER") "CC1206_100UF_6.3V_20%_X5R")
        (field (name "MANUFACTURER") "GENERIC")
        (field (name "AUTHOR") "CERN DEM JLC")
      )
      (libsource (lib "Capacitors") (part "Capacitor - non polarized"))
    )
    (comp (ref "C464")
      (value "100uF")
      (footprint "CAPC3216X180N")
      (description "Non-polarised capacitor")
      (fields
        (field (name "MANUFACTURER PART NUMBER") "CC1206_100UF_6.3V_20%_X5R")
        (field (name "MANUFACTURER") "GENERIC")
        (field (name "AUTHOR") "CERN DEM JLC")
      )
      (libsource (lib "Capacitors") (part "Capacitor - non polarized"))
    )
    (comp (ref "C465")
      (value "100uF")
      (footprint "CAPC3216X180N")
      (description "Non-polarised capacitor")
      (fields
        (field (name "MANUFACTURER PART NUMBER") "CC1206_100UF_6.3V_20%_X5R")
        (field (name "MANUFACTURER") "GENERIC")
        (field (name "AUTHOR") "CERN DEM JLC")
      )
      (libsource (lib "Capacitors") (part "Capacitor - non polarized"))
    )
    (comp (ref "C466")
      (value "100uF")
      (footprint "CAPC3216X180N")
      (description "Non-polarised capacitor")
      (fields
        (field (name "MANUFACTURER PART NUMBER") "CC1206_100UF_6.3V_20%_X5R")
        (field (name "MANUFACTURER") "GENERIC")
        (field (name "AUTHOR") "CERN DEM JLC")
      )
      (libsource (lib "Capacitors") (part "Capacitor - non polarized"))
    )
    (comp (ref "C467")
      (value "100uF")
      (footprint "CAPC3216X180N")
      (description "Non-polarised capacitor")
      (fields
        (field (name "MANUFACTURER PART NUMBER") "CC1206_100UF_6.3V_20%_X5R")
        (field (name "MANUFACTURER") "GENERIC")
        (field (name "AUTHOR") "CERN DEM JLC")
      )
      (libsource (lib "Capacitors") (part "Capacitor - non polarized"))
    )
    (comp (ref "C468")
      (value "100uF")
      (footprint "CAPC3216X180N")
      (description "Non-polarised capacitor")
      (fields
        (field (name "MANUFACTURER PART NUMBER") "CC1206_100UF_6.3V_20%_X5R")
        (field (name "MANUFACTURER") "GENERIC")
        (field (name "AUTHOR") "CERN DEM JLC")
      )
      (libsource (lib "Capacitors") (part "Capacitor - non polarized"))
    )
    (comp (ref "C469")
      (value "100uF")
      (footprint "CAPC3216X180N")
      (description "Non-polarised capacitor")
      (fields
        (field (name "MANUFACTURER PART NUMBER") "CC1206_100UF_6.3V_20%_X5R")
        (field (name "MANUFACTURER") "GENERIC")
        (field (name "AUTHOR") "CERN DEM JLC")
      )
      (libsource (lib "Capacitors") (part "Capacitor - non polarized"))
    )
    (comp (ref "C470")
      (value "100uF")
      (footprint "CAPC3216X180N")
      (description "Non-polarised capacitor")
      (fields
        (field (name "MANUFACTURER PART NUMBER") "CC1206_100UF_6.3V_20%_X5R")
        (field (name "MANUFACTURER") "GENERIC")
        (field (name "AUTHOR") "CERN DEM JLC")
      )
      (libsource (lib "Capacitors") (part "Capacitor - non polarized"))
    )
    (comp (ref "C471")
      (value "100uF")
      (footprint "CAPC3216X180N")
      (description "Non-polarised capacitor")
      (fields
        (field (name "MANUFACTURER PART NUMBER") "CC1206_100UF_6.3V_20%_X5R")
        (field (name "MANUFACTURER") "GENERIC")
        (field (name "AUTHOR") "CERN DEM JLC")
      )
      (libsource (lib "Capacitors") (part "Capacitor - non polarized"))
    )
    (comp (ref "C472")
      (value "100uF")
      (footprint "CAPC3216X180N")
      (description "Non-polarised capacitor")
      (fields
        (field (name "MANUFACTURER PART NUMBER") "CC1206_100UF_6.3V_20%_X5R")
        (field (name "MANUFACTURER") "GENERIC")
        (field (name "AUTHOR") "CERN DEM JLC")
      )
      (libsource (lib "Capacitors") (part "Capacitor - non polarized"))
    )
    (comp (ref "C473")
      (value "100uF")
      (footprint "CAPC3216X180N")
      (description "Non-polarised capacitor")
      (fields
        (field (name "MANUFACTURER PART NUMBER") "CC1206_100UF_6.3V_20%_X5R")
        (field (name "MANUFACTURER") "GENERIC")
        (field (name "AUTHOR") "CERN DEM JLC")
      )
      (libsource (lib "Capacitors") (part "Capacitor - non polarized"))
    )
    (comp (ref "C474")
      (value "100uF")
      (footprint "CAPC3216X180N")
      (description "Non-polarised capacitor")
      (fields
        (field (name "MANUFACTURER PART NUMBER") "CC1206_100UF_6.3V_20%_X5R")
        (field (name "MANUFACTURER") "GENERIC")
        (field (name "AUTHOR") "CERN DEM JLC")
      )
      (libsource (lib "Capacitors") (part "Capacitor - non polarized"))
    )
    (comp (ref "C475")
      (value "100uF")
      (footprint "CAPC3216X180N")
      (description "Non-polarised capacitor")
      (fields
        (field (name "MANUFACTURER PART NUMBER") "CC1206_100UF_6.3V_20%_X5R")
        (field (name "MANUFACTURER") "GENERIC")
        (field (name "AUTHOR") "CERN DEM JLC")
      )
      (libsource (lib "Capacitors") (part "Capacitor - non polarized"))
    )
    (comp (ref "C476")
      (value "100uF")
      (footprint "CAPC3216X180N")
      (description "Non-polarised capacitor")
      (fields
        (field (name "MANUFACTURER PART NUMBER") "CC1206_100UF_6.3V_20%_X5R")
        (field (name "MANUFACTURER") "GENERIC")
        (field (name "AUTHOR") "CERN DEM JLC")
      )
      (libsource (lib "Capacitors") (part "Capacitor - non polarized"))
    )
    (comp (ref "C477")
      (value "100uF")
      (footprint "CAPC3216X180N")
      (description "Non-polarised capacitor")
      (fields
        (field (name "MANUFACTURER PART NUMBER") "CC1206_100UF_6.3V_20%_X5R")
        (field (name "MANUFACTURER") "GENERIC")
        (field (name "AUTHOR") "CERN DEM JLC")
      )
      (libsource (lib "Capacitors") (part "Capacitor - non polarized"))
    )
    (comp (ref "C478")
      (value "100uF")
      (footprint "CAPC3216X180N")
      (description "Non-polarised capacitor")
      (fields
        (field (name "MANUFACTURER PART NUMBER") "CC1206_100UF_6.3V_20%_X5R")
        (field (name "MANUFACTURER") "GENERIC")
        (field (name "AUTHOR") "CERN DEM JLC")
      )
      (libsource (lib "Capacitors") (part "Capacitor - non polarized"))
    )
    (comp (ref "C479")
      (value "100uF")
      (footprint "CAPC3216X180N")
      (description "Non-polarised capacitor")
      (fields
        (field (name "MANUFACTURER PART NUMBER") "CC1206_100UF_6.3V_20%_X5R")
        (field (name "MANUFACTURER") "GENERIC")
        (field (name "AUTHOR") "CERN DEM JLC")
      )
      (libsource (lib "Capacitors") (part "Capacitor - non polarized"))
    )
    (comp (ref "C480")
      (value "100uF")
      (footprint "CAPC3216X180N")
      (description "Non-polarised capacitor")
      (fields
        (field (name "MANUFACTURER PART NUMBER") "CC1206_100UF_6.3V_20%_X5R")
        (field (name "MANUFACTURER") "GENERIC")
        (field (name "AUTHOR") "CERN DEM JLC")
      )
      (libsource (lib "Capacitors") (part "Capacitor - non polarized"))
    )
    (comp (ref "C481")
      (value "100uF")
      (footprint "CAPC3216X180N")
      (description "Non-polarised capacitor")
      (fields
        (field (name "MANUFACTURER PART NUMBER") "CC1206_100UF_6.3V_20%_X5R")
        (field (name "MANUFACTURER") "GENERIC")
        (field (name "AUTHOR") "CERN DEM JLC")
      )
      (libsource (lib "Capacitors") (part "Capacitor - non polarized"))
    )
    (comp (ref "C482")
      (value "100uF")
      (footprint "CAPC3216X180N")
      (description "Non-polarised capacitor")
      (fields
        (field (name "MANUFACTURER PART NUMBER") "CC1206_100UF_6.3V_20%_X5R")
        (field (name "MANUFACTURER") "GENERIC")
        (field (name "AUTHOR") "CERN DEM JLC")
      )
      (libsource (lib "Capacitors") (part "Capacitor - non polarized"))
    )
    (comp (ref "C483")
      (value "100uF")
      (footprint "CAPC3216X180N")
      (description "Non-polarised capacitor")
      (fields
        (field (name "MANUFACTURER PART NUMBER") "CC1206_100UF_6.3V_20%_X5R")
        (field (name "MANUFACTURER") "GENERIC")
        (field (name "AUTHOR") "CERN DEM JLC")
      )
      (libsource (lib "Capacitors") (part "Capacitor - non polarized"))
    )
    (comp (ref "C484")
      (value "100uF")
      (footprint "CAPC3216X180N")
      (description "Non-polarised capacitor")
      (fields
        (field (name "MANUFACTURER PART NUMBER") "CC1206_100UF_6.3V_20%_X5R")
        (field (name "MANUFACTURER") "GENERIC")
        (field (name "AUTHOR") "CERN DEM JLC")
      )
      (libsource (lib "Capacitors") (part "Capacitor - non polarized"))
    )
    (comp (ref "C485")
      (value "100uF")
      (footprint "CAPC3216X180N")
      (description "Non-polarised capacitor")
      (fields
        (field (name "MANUFACTURER PART NUMBER") "CC1206_100UF_6.3V_20%_X5R")
        (field (name "MANUFACTURER") "GENERIC")
        (field (name "AUTHOR") "CERN DEM JLC")
      )
      (libsource (lib "Capacitors") (part "Capacitor - non polarized"))
    )
    (comp (ref "C486")
      (value "100uF")
      (footprint "CAPC3216X180N")
      (description "Non-polarised capacitor")
      (fields
        (field (name "MANUFACTURER PART NUMBER") "CC1206_100UF_6.3V_20%_X5R")
        (field (name "MANUFACTURER") "GENERIC")
        (field (name "AUTHOR") "CERN DEM JLC")
      )
      (libsource (lib "Capacitors") (part "Capacitor - non polarized"))
    )
    (comp (ref "C487")
      (value "100uF")
      (footprint "CAPC3216X180N")
      (description "Non-polarised capacitor")
      (fields
        (field (name "MANUFACTURER PART NUMBER") "CC1206_100UF_6.3V_20%_X5R")
        (field (name "MANUFACTURER") "GENERIC")
        (field (name "AUTHOR") "CERN DEM JLC")
      )
      (libsource (lib "Capacitors") (part "Capacitor - non polarized"))
    )
    (comp (ref "C488")
      (value "100uF")
      (footprint "CAPC3216X180N")
      (description "Non-polarised capacitor")
      (fields
        (field (name "MANUFACTURER PART NUMBER") "CC1206_100UF_6.3V_20%_X5R")
        (field (name "MANUFACTURER") "GENERIC")
        (field (name "AUTHOR") "CERN DEM JLC")
      )
      (libsource (lib "Capacitors") (part "Capacitor - non polarized"))
    )
    (comp (ref "C489")
      (value "100uF")
      (footprint "CAPC3216X180N")
      (description "Non-polarised capacitor")
      (fields
        (field (name "MANUFACTURER PART NUMBER") "CC1206_100UF_6.3V_20%_X5R")
        (field (name "MANUFACTURER") "GENERIC")
        (field (name "AUTHOR") "CERN DEM JLC")
      )
      (libsource (lib "Capacitors") (part "Capacitor - non polarized"))
    )
    (comp (ref "C490")
      (value "100uF")
      (footprint "CAPC3216X180N")
      (description "Non-polarised capacitor")
      (fields
        (field (name "MANUFACTURER PART NUMBER") "CC1206_100UF_6.3V_20%_X5R")
        (field (name "MANUFACTURER") "GENERIC")
        (field (name "AUTHOR") "CERN DEM JLC")
      )
      (libsource (lib "Capacitors") (part "Capacitor - non polarized"))
    )
    (comp (ref "C491")
      (value "100uF")
      (footprint "CAPC3216X180N")
      (description "Non-polarised capacitor")
      (fields
        (field (name "MANUFACTURER PART NUMBER") "CC1206_100UF_6.3V_20%_X5R")
        (field (name "MANUFACTURER") "GENERIC")
        (field (name "AUTHOR") "CERN DEM JLC")
      )
      (libsource (lib "Capacitors") (part "Capacitor - non polarized"))
    )
    (comp (ref "C492")
      (value "100uF")
      (footprint "CAPC3216X180N")
      (description "Non-polarised capacitor")
      (fields
        (field (name "MANUFACTURER PART NUMBER") "CC1206_100UF_6.3V_20%_X5R")
        (field (name "MANUFACTURER") "GENERIC")
        (field (name "AUTHOR") "CERN DEM JLC")
      )
      (libsource (lib "Capacitors") (part "Capacitor - non polarized"))
    )
    (comp (ref "C493")
      (value "100uF")
      (footprint "CAPC3216X180N")
      (description "Non-polarised capacitor")
      (fields
        (field (name "MANUFACTURER PART NUMBER") "CC1206_100UF_6.3V_20%_X5R")
        (field (name "MANUFACTURER") "GENERIC")
        (field (name "AUTHOR") "CERN DEM JLC")
      )
      (libsource (lib "Capacitors") (part "Capacitor - non polarized"))
    )
    (comp (ref "C494")
      (value "100uF")
      (footprint "CAPC3216X180N")
      (description "Non-polarised capacitor")
      (fields
        (field (name "MANUFACTURER PART NUMBER") "CC1206_100UF_6.3V_20%_X5R")
        (field (name "MANUFACTURER") "GENERIC")
        (field (name "AUTHOR") "CERN DEM JLC")
      )
      (libsource (lib "Capacitors") (part "Capacitor - non polarized"))
    )
    (comp (ref "C495")
      (value "100uF")
      (footprint "CAPC3216X180N")
      (description "Non-polarised capacitor")
      (fields
        (field (name "MANUFACTURER PART NUMBER") "CC1206_100UF_6.3V_20%_X5R")
        (field (name "MANUFACTURER") "GENERIC")
        (field (name "AUTHOR") "CERN DEM JLC")
      )
      (libsource (lib "Capacitors") (part "Capacitor - non polarized"))
    )
    (comp (ref "C496")
      (value "100uF")
      (footprint "CAPC3216X180N")
      (description "Non-polarised capacitor")
      (fields
        (field (name "MANUFACTURER PART NUMBER") "CC1206_100UF_6.3V_20%_X5R")
        (field (name "MANUFACTURER") "GENERIC")
        (field (name "AUTHOR") "CERN DEM JLC")
      )
      (libsource (lib "Capacitors") (part "Capacitor - non polarized"))
    )
    (comp (ref "C497")
      (value "100uF")
      (footprint "CAPC3216X180N")
      (description "Non-polarised capacitor")
      (fields
        (field (name "MANUFACTURER PART NUMBER") "CC1206_100UF_6.3V_20%_X5R")
        (field (name "MANUFACTURER") "GENERIC")
        (field (name "AUTHOR") "CERN DEM JLC")
      )
      (libsource (lib "Capacitors") (part "Capacitor - non polarized"))
    )
    (comp (ref "C498")
      (value "100uF")
      (footprint "CAPC3216X180N")
      (description "Non-polarised capacitor")
      (fields
        (field (name "MANUFACTURER PART NUMBER") "CC1206_100UF_6.3V_20%_X5R")
        (field (name "MANUFACTURER") "GENERIC")
        (field (name "AUTHOR") "CERN DEM JLC")
      )
      (libsource (lib "Capacitors") (part "Capacitor - non polarized"))
    )
    (comp (ref "C499")
      (value "100uF")
      (footprint "CAPC3216X180N")
      (description "Non-polarised capacitor")
      (fields
        (field (name "MANUFACTURER PART NUMBER") "CC1206_100UF_6.3V_20%_X5R")
        (field (name "MANUFACTURER") "GENERIC")
        (field (name "AUTHOR") "CERN DEM JLC")
      )
      (libsource (lib "Capacitors") (part "Capacitor - non polarized"))
    )
    (comp (ref "C500")
      (value "100uF")
      (footprint "CAPC3216X180N")
      (description "Non-polarised capacitor")
      (fields
        (field (name "MANUFACTURER PART NUMBER") "CC1206_100UF_6.3V_20%_X5R")
        (field (name "MANUFACTURER") "GENERIC")
        (field (name "AUTHOR") "CERN DEM JLC")
      )
      (libsource (lib "Capacitors") (part "Capacitor - non polarized"))
    )
    (comp (ref "C521")
      (value "330uF")
      (footprint "CAPMP3528X210N")
      (description "Polarised capacitor")
      (fields
        (field (name "MANUFACTURER PART NUMBER") "T520B337M2R5ATE015")
        (field (name "MANUFACTURER") "KEMET")
        (field (name "AUTHOR") "CERN DEM JLC")
      )
      (libsource (lib "Capacitors") (part "Capacitor - polarized"))
    )
    (comp (ref "C522")
      (value "330uF")
      (footprint "CAPMP3528X210N")
      (description "Polarised capacitor")
      (fields
        (field (name "MANUFACTURER PART NUMBER") "T520B337M2R5ATE015")
        (field (name "MANUFACTURER") "KEMET")
        (field (name "AUTHOR") "CERN DEM JLC")
      )
      (libsource (lib "Capacitors") (part "Capacitor - polarized"))
    )
    (comp (ref "C523")
      (value "330uF")
      (footprint "CAPMP3528X210N")
      (description "Polarised capacitor")
      (fields
        (field (name "MANUFACTURER PART NUMBER") "T520B337M2R5ATE015")
        (field (name "MANUFACTURER") "KEMET")
        (field (name "AUTHOR") "CERN DEM JLC")
      )
      (libsource (lib "Capacitors") (part "Capacitor - polarized"))
    )
    (comp (ref "C524")
      (value "330uF")
      (footprint "CAPMP3528X210N")
      (description "Polarised capacitor")
      (fields
        (field (name "MANUFACTURER PART NUMBER") "T520B337M2R5ATE015")
        (field (name "MANUFACTURER") "KEMET")
        (field (name "AUTHOR") "CERN DEM JLC")
      )
      (libsource (lib "Capacitors") (part "Capacitor - polarized"))
    )
    (comp (ref "C525")
      (value "330uF")
      (footprint "CAPMP3528X210N")
      (description "Polarised capacitor")
      (fields
        (field (name "MANUFACTURER PART NUMBER") "T520B337M2R5ATE015")
        (field (name "MANUFACTURER") "KEMET")
        (field (name "AUTHOR") "CERN DEM JLC")
      )
      (libsource (lib "Capacitors") (part "Capacitor - polarized"))
    )
    (comp (ref "C526")
      (value "330uF")
      (footprint "CAPMP3528X210N")
      (description "Polarised capacitor")
      (fields
        (field (name "MANUFACTURER PART NUMBER") "T520B337M2R5ATE015")
        (field (name "MANUFACTURER") "KEMET")
        (field (name "AUTHOR") "CERN DEM JLC")
      )
      (libsource (lib "Capacitors") (part "Capacitor - polarized"))
    )
    (comp (ref "C527")
      (value "330uF")
      (footprint "CAPMP3528X210N")
      (description "Polarised capacitor")
      (fields
        (field (name "MANUFACTURER PART NUMBER") "T520B337M2R5ATE015")
        (field (name "MANUFACTURER") "KEMET")
        (field (name "AUTHOR") "CERN DEM JLC")
      )
      (libsource (lib "Capacitors") (part "Capacitor - polarized"))
    )
    (comp (ref "C528")
      (value "330uF")
      (footprint "CAPMP3528X210N")
      (description "Polarised capacitor")
      (fields
        (field (name "MANUFACTURER PART NUMBER") "T520B337M2R5ATE015")
        (field (name "MANUFACTURER") "KEMET")
        (field (name "AUTHOR") "CERN DEM JLC")
      )
      (libsource (lib "Capacitors") (part "Capacitor - polarized"))
    )
    (comp (ref "C529")
      (value "47uF")
      (footprint "CAPC3225X270N")
      (description "Non-polarised capacitor")
      (fields
        (field (name "MANUFACTURER PART NUMBER") "CC1210_47UF_6.3V_10%_X5R")
        (field (name "MANUFACTURER") "GENERIC")
        (field (name "AUTHOR") "CERN DEM JLC")
      )
      (libsource (lib "Capacitors") (part "Capacitor - non polarized"))
    )
  )
  (nets
    (net (code "1") (name "GND") (class "Default")
      (node (ref "C147") (pin "1") (pinfunction "1_1") (pintype "passive"))
      (node (ref "C148") (pin "1") (pinfunction "1_1") (pintype "passive"))
      (node (ref "C149") (pin "1") (pinfunction "1_1") (pintype "passive"))
      (node (ref "C150") (pin "1") (pinfunction "1_1") (pintype "passive"))
      (node (ref "C151") (pin "1") (pinfunction "1_1") (pintype "passive"))
      (node (ref "C152") (pin "1") (pinfunction "1_1") (pintype "passive"))
      (node (ref "C153") (pin "1") (pinfunction "1_1") (pintype "passive"))
      (node (ref "C154") (pin "1") (pinfunction "1_1") (pintype "passive"))
      (node (ref "C155") (pin "1") (pinfunction "1_1") (pintype "passive"))
      (node (ref "C156") (pin "1") (pinfunction "1_1") (pintype "passive"))
      (node (ref "C157") (pin "1") (pinfunction "1_1") (pintype "passive"))
      (node (ref "C158") (pin "1") (pinfunction "1_1") (pintype "passive"))
      (node (ref "C159") (pin "1") (pinfunction "1_1") (pintype "passive"))
      (node (ref "C160") (pin "1") (pinfunction "1_1") (pintype "passive"))
      (node (ref "C161") (pin "1") (pinfunction "1_1") (pintype "passive"))
      (node (ref "C162") (pin "1") (pinfunction "1_1") (pintype "passive"))
      (node (ref "C163") (pin "1") (pinfunction "1_1") (pintype "passive"))
      (node (ref "C164") (pin "1") (pinfunction "1_1") (pintype "passive"))
      (node (ref "C165") (pin "1") (pinfunction "1_1") (pintype "passive"))
      (node (ref "C166") (pin "1") (pinfunction "1_1") (pintype "passive"))
      (node (ref "C167") (pin "1") (pinfunction "1_1") (pintype "passive"))
      (node (ref "C364") (pin "1") (pinfunction "1_1") (pintype "passive"))
      (node (ref "C365") (pin "1") (pinfunction "1_1") (pintype "passive"))
      (node (ref "C366") (pin "1") (pinfunction "1_1") (pintype "passive"))
      (node (ref "C367") (pin "1") (pinfunction "1_1") (pintype "passive"))
      (node (ref "C368") (pin "1") (pinfunction "1_1") (pintype "passive"))
      (node (ref "C369") (pin "1") (pinfunction "1_1") (pintype "passive"))
      (node (ref "C370") (pin "1") (pinfunction "1_1") (pintype "passive"))
      (node (ref "C371") (pin "1") (pinfunction "1_1") (pintype "passive"))
      (node (ref "C372") (pin "1") (pinfunction "1_1") (pintype "passive"))
      (node (ref "C373") (pin "1") (pinfunction "1_1") (pintype "passive"))
      (node (ref "C374") (pin "1") (pinfunction "1_1") (pintype "passive"))
      (node (ref "C375") (pin "1") (pinfunction "1_1") (pintype "passive"))
      (node (ref "C376") (pin "1") (pinfunction "1_1") (pintype "passive"))
      (node (ref "C377") (pin "1") (pinfunction "1_1") (pintype "passive"))
      (node (ref "C378") (pin "1") (pinfunction "1_1") (pintype "passive"))
      (node (ref "C379") (pin "1") (pinfunction "1_1") (pintype "passive"))
      (node (ref "C380") (pin "1") (pinfunction "1_1") (pintype "passive"))
      (node (ref "C381") (pin "1") (pinfunction "1_1") (pintype "passive"))
      (node (ref "C382") (pin "1") (pinfunction "1_1") (pintype "passive"))
      (node (ref "C383") (pin "1") (pinfunction "1_1") (pintype "passive"))
      (node (ref "C384") (pin "1") (pinfunction "1_1") (pintype "passive"))
      (node (ref "C385") (pin "1") (pinfunction "1_1") (pintype "passive"))
      (node (ref "C386") (pin "1") (pinfunction "1_1") (pintype "passive"))
      (node (ref "C387") (pin "1") (pinfunction "1_1") (pintype "passive"))
      (node (ref "C388") (pin "1") (pinfunction "1_1") (pintype "passive"))
      (node (ref "C389") (pin "1") (pinfunction "1_1") (pintype "passive"))
      (node (ref "C390") (pin "1") (pinfunction "1_1") (pintype "passive"))
      (node (ref "C391") (pin "1") (pinfunction "1_1") (pintype "passive"))
      (node (ref "C392") (pin "1") (pinfunction "1_1") (pintype "passive"))
      (node (ref "C393") (pin "1") (pinfunction "1_1") (pintype "passive"))
      (node (ref "C394") (pin "1") (pinfunction "1_1") (pintype "passive"))
      (node (ref "C395") (pin "1") (pinfunction "1_1") (pintype "passive"))
      (node (ref "C396") (pin "1") (pinfunction "1_1") (pintype "passive"))
      (node (ref "C397") (pin "1") (pinfunction "1_1") (pintype "passive"))
      (node (ref "C398") (pin "1") (pinfunction "1_1") (pintype "passive"))
      (node (ref "C399") (pin "1") (pinfunction "1_1") (pintype "passive"))
      (node (ref "C400") (pin "1") (pinfunction "1_1") (pintype "passive"))
      (node (ref "C401") (pin "1") (pinfunction "1_1") (pintype "passive"))
      (node (ref "C402") (pin "1") (pinfunction "1_1") (pintype "passive"))
      (node (ref "C403") (pin "1") (pinfunction "1_1") (pintype "passive"))
      (node (ref "C404") (pin "1") (pinfunction "1_1") (pintype "passive"))
      (node (ref "C405") (pin "1") (pinfunction "1_1") (pintype "passive"))
      (node (ref "C406") (pin "1") (pinfunction "1_1") (pintype "passive"))
      (node (ref "C407") (pin "1") (pinfunction "1_1") (pintype "passive"))
      (node (ref "C408") (pin "1") (pinfunction "1_1") (pintype "passive"))
      (node (ref "C409") (pin "1") (pinfunction "1_1") (pintype "passive"))
      (node (ref "C410") (pin "1") (pinfunction "1_1") (pintype "passive"))
      (node (ref "C411") (pin "1") (pinfunction "1_1") (pintype "passive"))
      (node (ref "C412") (pin "1") (pinfunction "1_1") (pintype "passive"))
      (node (ref "C413") (pin "1") (pinfunction "1_1") (pintype "passive"))
      (node (ref "C414") (pin "1") (pinfunction "1_1") (pintype "passive"))
      (node (ref "C415") (pin "1") (pinfunction "1_1") (pintype "passive"))
      (node (ref "C416") (pin "1") (pinfunction "1_1") (pintype "passive"))
      (node (ref "C417") (pin "1") (pinfunction "1_1") (pintype "passive"))
      (node (ref "C418") (pin "1") (pinfunction "1_1") (pintype "passive"))
      (node (ref "C419") (pin "1") (pinfunction "1_1") (pintype "passive"))
      (node (ref "C420") (pin "1") (pinfunction "1_1") (pintype "passive"))
      (node (ref "C421") (pin "1") (pinfunction "1_1") (pintype "passive"))
      (node (ref "C422") (pin "1") (pinfunction "1_1") (pintype "passive"))
      (node (ref "C423") (pin "1") (pinfunction "1_1") (pintype "passive"))
      (node (ref "C424") (pin "1") (pinfunction "1_1") (pintype "passive"))
      (node (ref "C425") (pin "1") (pinfunction "1_1") (pintype "passive"))
      (node (ref "C426") (pin "1") (pinfunction "1_1") (pintype "passive"))
      (node (ref "C427") (pin "1") (pinfunction "1_1") (pintype "passive"))
      (node (ref "C428") (pin "1") (pinfunction "1_1") (pintype "passive"))
      (node (ref "C429") (pin "1") (pinfunction "1_1") (pintype "passive"))
      (node (ref "C463") (pin "1") (pinfunction "1_1") (pintype "passive"))
      (node (ref "C464") (pin "1") (pinfunction "1_1") (pintype "passive"))
      (node (ref "C465") (pin "1") (pinfunction "1_1") (pintype "passive"))
      (node (ref "C466") (pin "1") (pinfunction "1_1") (pintype "passive"))
      (node (ref "C467") (pin "1") (pinfunction "1_1") (pintype "passive"))
      (node (ref "C468") (pin "1") (pinfunction "1_1") (pintype "passive"))
      (node (ref "C469") (pin "1") (pinfunction "1_1") (pintype "passive"))
      (node (ref "C470") (pin "1") (pinfunction "1_1") (pintype "passive"))
      (node (ref "C471") (pin "1") (pinfunction "1_1") (pintype "passive"))
      (node (ref "C472") (pin "1") (pinfunction "1_1") (pintype "passive"))
      (node (ref "C473") (pin "1") (pinfunction "1_1") (pintype "passive"))
      (node (ref "C474") (pin "1") (pinfunction "1_1") (pintype "passive"))
      (node (ref "C475") (pin "1") (pinfunction "1_1") (pintype "passive"))
      (node (ref "C476") (pin "1") (pinfunction "1_1") (pintype "passive"))
      (node (ref "C477") (pin "1") (pinfunction "1_1") (pintype "passive"))
      (node (ref "C478") (pin "1") (pinfunction "1_1") (pintype "passive"))
      (node (ref "C479") (pin "1") (pinfunction "1_1") (pintype "passive"))
      (node (ref "C480") (pin "1") (pinfunction "1_1") (pintype "passive"))
      (node (ref "C481") (pin "1") (pinfunction "1_1") (pintype "passive"))
      (node (ref "C482") (pin "1") (pinfunction "1_1") (pintype "passive"))
      (node (ref "C483") (pin "1") (pinfunction "1_1") (pintype "passive"))
      (node (ref "C484") (pin "1") (pinfunction "1_1") (pintype "passive"))
      (node (ref "C485") (pin "1") (pinfunction "1_1") (pintype "passive"))
      (node (ref "C486") (pin "1") (pinfunction "1_1") (pintype "passive"))
      (node (ref "C487") (pin "1") (pinfunction "1_1") (pintype "passive"))
      (node (ref "C488") (pin "1") (pinfunction "1_1") (pintype "passive"))
      (node (ref "C489") (pin "1") (pinfunction "1_1") (pintype "passive"))
      (node (ref "C490") (pin "1") (pinfunction "1_1") (pintype "passive"))
      (node (ref "C491") (pin "1") (pinfunction "1_1") (pintype "passive"))
      (node (ref "C492") (pin "1") (pinfunction "1_1") (pintype "passive"))
      (node (ref "C493") (pin "1") (pinfunction "1_1") (pintype "passive"))
      (node (ref "C494") (pin "1") (pinfunction "1_1") (pintype "passive"))
      (node (ref "C495") (pin "1") (pinfunction "1_1") (pintype "passive"))
      (node (ref "C496") (pin "1") (pinfunction "1_1") (pintype "passive"))
      (node (ref "C497") (pin "1") (pinfunction "1_1") (pintype "passive"))
      (node (ref "C498") (pin "1") (pinfunction "1_1") (pintype "passive"))
      (node (ref "C499") (pin "1") (pinfunction "1_1") (pintype "passive"))
      (node (ref "C500") (pin "1") (pinfunction "1_1") (pintype "passive"))
      (node (ref "C521") (pin "2") (pinfunction "2_2") (pintype "passive"))
      (node (ref "C522") (pin "2") (pinfunction "2_2") (pintype "passive"))
      (node (ref "C523") (pin "2") (pinfunction "2_2") (pintype "passive"))
      (node (ref "C524") (pin "2") (pinfunction "2_2") (pintype "passive"))
      (node (ref "C525") (pin "2") (pinfunction "2_2") (pintype "passive"))
      (node (ref "C526") (pin "2") (pinfunction "2_2") (pintype "passive"))
      (node (ref "C527") (pin "2") (pinfunction "2_2") (pintype "passive"))
      (node (ref "C528") (pin "2") (pinfunction "2_2") (pintype "passive"))
      (node (ref "C529") (pin "1") (pinfunction "1_1") (pintype "passive"))
    )
    (net (code "2") (name "MGTAVCC") (class "Default")
      (node (ref "C153") (pin "2") (pinfunction "2_2") (pintype "passive"))
      (node (ref "C154") (pin "2") (pinfunction "2_2") (pintype "passive"))
      (node (ref "C155") (pin "2") (pinfunction "2_2") (pintype "passive"))
      (node (ref "C156") (pin "2") (pinfunction "2_2") (pintype "passive"))
      (node (ref "C157") (pin "2") (pinfunction "2_2") (pintype "passive"))
      (node (ref "C158") (pin "2") (pinfunction "2_2") (pintype "passive"))
      (node (ref "C160") (pin "2") (pinfunction "2_2") (pintype "passive"))
      (node (ref "C162") (pin "2") (pinfunction "2_2") (pintype "passive"))
      (node (ref "C164") (pin "2") (pinfunction "2_2") (pintype "passive"))
      (node (ref "C167") (pin "2") (pinfunction "2_2") (pintype "passive"))
      (node (ref "C407") (pin "2") (pinfunction "2_2") (pintype "passive"))
      (node (ref "C411") (pin "2") (pinfunction "2_2") (pintype "passive"))
      (node (ref "C412") (pin "2") (pinfunction "2_2") (pintype "passive"))
      (node (ref "C415") (pin "2") (pinfunction "2_2") (pintype "passive"))
      (node (ref "C417") (pin "2") (pinfunction "2_2") (pintype "passive"))
      (node (ref "C477") (pin "2") (pinfunction "2_2") (pintype "passive"))
      (node (ref "C478") (pin "2") (pinfunction "2_2") (pintype "passive"))
      (node (ref "C479") (pin "2") (pinfunction "2_2") (pintype "passive"))
      (node (ref "C480") (pin "2") (pinfunction "2_2") (pintype "passive"))
      (node (ref "C481") (pin "2") (pinfunction "2_2") (pintype "passive"))
      (node (ref "C482") (pin "2") (pinfunction "2_2") (pintype "passive"))
      (node (ref "C483") (pin "2") (pinfunction "2_2") (pintype "passive"))
      (node (ref "C484") (pin "2") (pinfunction "2_2") (pintype "passive"))
      (node (ref "C485") (pin "2") (pinfunction "2_2") (pintype "passive"))
      (node (ref "C486") (pin "2") (pinfunction "2_2") (pintype "passive"))
      (node (ref "C487") (pin "2") (pinfunction "2_2") (pintype "passive"))
      (node (ref "C488") (pin "2") (pinfunction "2_2") (pintype "passive"))
    )
    (net (code "3") (name "MGTAVTT") (class "Default")
      (node (ref "C159") (pin "2") (pinfunction "2_2") (pintype "passive"))
      (node (ref "C161") (pin "2") (pinfunction "2_2") (pintype "passive"))
      (node (ref "C163") (pin "2") (pinfunction "2_2") (pintype "passive"))
      (node (ref "C165") (pin "2") (pinfunction "2_2") (pintype "passive"))
      (node (ref "C166") (pin "2") (pinfunction "2_2") (pintype "passive"))
      (node (ref "C406") (pin "2") (pinfunction "2_2") (pintype "passive"))
      (node (ref "C408") (pin "2") (pinfunction "2_2") (pintype "passive"))
      (node (ref "C410") (pin "2") (pinfunction "2_2") (pintype "passive"))
      (node (ref "C413") (pin "2") (pinfunction "2_2") (pintype "passive"))
      (node (ref "C414") (pin "2") (pinfunction "2_2") (pintype "passive"))
      (node (ref "C489") (pin "2") (pinfunction "2_2") (pintype "passive"))
      (node (ref "C490") (pin "2") (pinfunction "2_2") (pintype "passive"))
      (node (ref "C491") (pin "2") (pinfunction "2_2") (pintype "passive"))
      (node (ref "C492") (pin "2") (pinfunction "2_2") (pintype "passive"))
      (node (ref "C493") (pin "2") (pinfunction "2_2") (pintype "passive"))
      (node (ref "C494") (pin "2") (pinfunction "2_2") (pintype "passive"))
      (node (ref "C495") (pin "2") (pinfunction "2_2") (pintype "passive"))
      (node (ref "C496") (pin "2") (pinfunction "2_2") (pintype "passive"))
      (node (ref "C497") (pin "2") (pinfunction "2_2") (pintype "passive"))
      (node (ref "C498") (pin "2") (pinfunction "2_2") (pintype "passive"))
      (node (ref "C499") (pin "2") (pinfunction "2_2") (pintype "passive"))
      (node (ref "C500") (pin "2") (pinfunction "2_2") (pintype "passive"))
    )
    (net (code "4") (name "MGTVCCAUX") (class "Default")
      (node (ref "C405") (pin "2") (pinfunction "2_2") (pintype "passive"))
      (node (ref "C409") (pin "2") (pinfunction "2_2") (pintype "passive"))
      (node (ref "C416") (pin "2") (pinfunction "2_2") (pintype "passive"))
      (node (ref "C418") (pin "2") (pinfunction "2_2") (pintype "passive"))
      (node (ref "C419") (pin "2") (pinfunction "2_2") (pintype "passive"))
    )
    (net (code "5") (name "P1V5") (class "Default")
      (node (ref "C364") (pin "2") (pinfunction "2_2") (pintype "passive"))
      (node (ref "C365") (pin "2") (pinfunction "2_2") (pintype "passive"))
      (node (ref "C366") (pin "2") (pinfunction "2_2") (pintype "passive"))
      (node (ref "C367") (pin "2") (pinfunction "2_2") (pintype "passive"))
      (node (ref "C424") (pin "2") (pinfunction "2_2") (pintype "passive"))
      (node (ref "C425") (pin "2") (pinfunction "2_2") (pintype "passive"))
      (node (ref "C427") (pin "2") (pinfunction "2_2") (pintype "passive"))
      (node (ref "C473") (pin "2") (pinfunction "2_2") (pintype "passive"))
      (node (ref "C475") (pin "2") (pinfunction "2_2") (pintype "passive"))
    )
    (net (code "6") (name "P1V8") (class "Default")
      (node (ref "C368") (pin "2") (pinfunction "2_2") (pintype "passive"))
      (node (ref "C369") (pin "2") (pinfunction "2_2") (pintype "passive"))
      (node (ref "C395") (pin "2") (pinfunction "2_2") (pintype "passive"))
      (node (ref "C396") (pin "2") (pinfunction "2_2") (pintype "passive"))
      (node (ref "C397") (pin "2") (pinfunction "2_2") (pintype "passive"))
      (node (ref "C398") (pin "2") (pinfunction "2_2") (pintype "passive"))
      (node (ref "C399") (pin "2") (pinfunction "2_2") (pintype "passive"))
      (node (ref "C400") (pin "2") (pinfunction "2_2") (pintype "passive"))
      (node (ref "C401") (pin "2") (pinfunction "2_2") (pintype "passive"))
      (node (ref "C402") (pin "2") (pinfunction "2_2") (pintype "passive"))
      (node (ref "C403") (pin "2") (pinfunction "2_2") (pintype "passive"))
      (node (ref "C404") (pin "2") (pinfunction "2_2") (pintype "passive"))
      (node (ref "C420") (pin "2") (pinfunction "2_2") (pintype "passive"))
      (node (ref "C421") (pin "2") (pinfunction "2_2") (pintype "passive"))
      (node (ref "C426") (pin "2") (pinfunction "2_2") (pintype "passive"))
      (node (ref "C428") (pin "2") (pinfunction "2_2") (pintype "passive"))
      (node (ref "C429") (pin "2") (pinfunction "2_2") (pintype "passive"))
      (node (ref "C471") (pin "2") (pinfunction "2_2") (pintype "passive"))
      (node (ref "C472") (pin "2") (pinfunction "2_2") (pintype "passive"))
      (node (ref "C474") (pin "2") (pinfunction "2_2") (pintype "passive"))
    )
    (net (code "7") (name "P3V3") (class "Default")
      (node (ref "C370") (pin "2") (pinfunction "2_2") (pintype "passive"))
      (node (ref "C371") (pin "2") (pinfunction "2_2") (pintype "passive"))
      (node (ref "C372") (pin "2") (pinfunction "2_2") (pintype "passive"))
      (node (ref "C373") (pin "2") (pinfunction "2_2") (pintype "passive"))
      (node (ref "C374") (pin "2") (pinfunction "2_2") (pintype "passive"))
      (node (ref "C375") (pin "2") (pinfunction "2_2") (pintype "passive"))
      (node (ref "C529") (pin "2") (pinfunction "2_2") (pintype "passive"))
    )
    (net (code "8") (name "VCCAUX") (class "Default")
      (node (ref "C376") (pin "2") (pinfunction "2_2") (pintype "passive"))
      (node (ref "C377") (pin "2") (pinfunction "2_2") (pintype "passive"))
      (node (ref "C378") (pin "2") (pinfunction "2_2") (pintype "passive"))
      (node (ref "C379") (pin "2") (pinfunction "2_2") (pintype "passive"))
      (node (ref "C387") (pin "2") (pinfunction "2_2") (pintype "passive"))
      (node (ref "C422") (pin "2") (pinfunction "2_2") (pintype "passive"))
      (node (ref "C423") (pin "2") (pinfunction "2_2") (pintype "passive"))
      (node (ref "C476") (pin "2") (pinfunction "2_2") (pintype "passive"))
    )
    (net (code "9") (name "VCCBRAM") (class "Default")
      (node (ref "C380") (pin "2") (pinfunction "2_2") (pintype "passive"))
      (node (ref "C381") (pin "2") (pinfunction "2_2") (pintype "passive"))
      (node (ref "C382") (pin "2") (pinfunction "2_2") (pintype "passive"))
      (node (ref "C383") (pin "2") (pinfunction "2_2") (pintype "passive"))
      (node (ref "C384") (pin "2") (pinfunction "2_2") (pintype "passive"))
      (node (ref "C385") (pin "2") (pinfunction "2_2") (pintype "passive"))
      (node (ref "C386") (pin "2") (pinfunction "2_2") (pintype "passive"))
      (node (ref "C463") (pin "2") (pinfunction "2_2") (pintype "passive"))
      (node (ref "C464") (pin "2") (pinfunction "2_2") (pintype "passive"))
      (node (ref "C465") (pin "2") (pinfunction "2_2") (pintype "passive"))
    )
    (net (code "10") (name "VCCINT") (class "Default")
      (node (ref "C147") (pin "2") (pinfunction "2_2") (pintype "passive"))
      (node (ref "C148") (pin "2") (pinfunction "2_2") (pintype "passive"))
      (node (ref "C149") (pin "2") (pinfunction "2_2") (pintype "passive"))
      (node (ref "C150") (pin "2") (pinfunction "2_2") (pintype "passive"))
      (node (ref "C151") (pin "2") (pinfunction "2_2") (pintype "passive"))
      (node (ref "C152") (pin "2") (pinfunction "2_2") (pintype "passive"))
      (node (ref "C388") (pin "2") (pinfunction "2_2") (pintype "passive"))
      (node (ref "C389") (pin "2") (pinfunction "2_2") (pintype "passive"))
      (node (ref "C390") (pin "2") (pinfunction "2_2") (pintype "passive"))
      (node (ref "C391") (pin "2") (pinfunction "2_2") (pintype "passive"))
      (node (ref "C392") (pin "2") (pinfunction "2_2") (pintype "passive"))
      (node (ref "C393") (pin "2") (pinfunction "2_2") (pintype "passive"))
      (node (ref "C394") (pin "2") (pinfunction "2_2") (pintype "passive"))
      (node (ref "C466") (pin "2") (pinfunction "2_2") (pintype "passive"))
      (node (ref "C467") (pin "2") (pinfunction "2_2") (pintype "passive"))
      (node (ref "C468") (pin "2") (pinfunction "2_2") (pintype "passive"))
      (node (ref "C469") (pin "2") (pinfunction "2_2") (pintype "passive"))
      (node (ref "C470") (pin "2") (pinfunction "2_2") (pintype "passive"))
      (node (ref "C521") (pin "1") (pinfunction "1_1") (pintype "passive"))
      (node (ref "C522") (pin "1") (pinfunction "1_1") (pintype "passive"))
      (node (ref "C523") (pin "1") (pinfunction "1_1") (pintype "passive"))
      (node (ref "C524") (pin "1") (pinfunction "1_1") (pintype "passive"))
      (node (ref "C525") (pin "1") (pinfunction "1_1") (pintype "passive"))
      (node (ref "C526") (pin "1") (pinfunction "1_1") (pintype "passive"))
      (node (ref "C527") (pin "1") (pinfunction "1_1") (pintype "passive"))
      (node (ref "C528") (pin "1") (pinfunction "1_1") (pintype "passive"))
    )
  )
)
